# CURRENT_MEASURE.net
KiCad netlist of a schematic drawn in Altium Designer
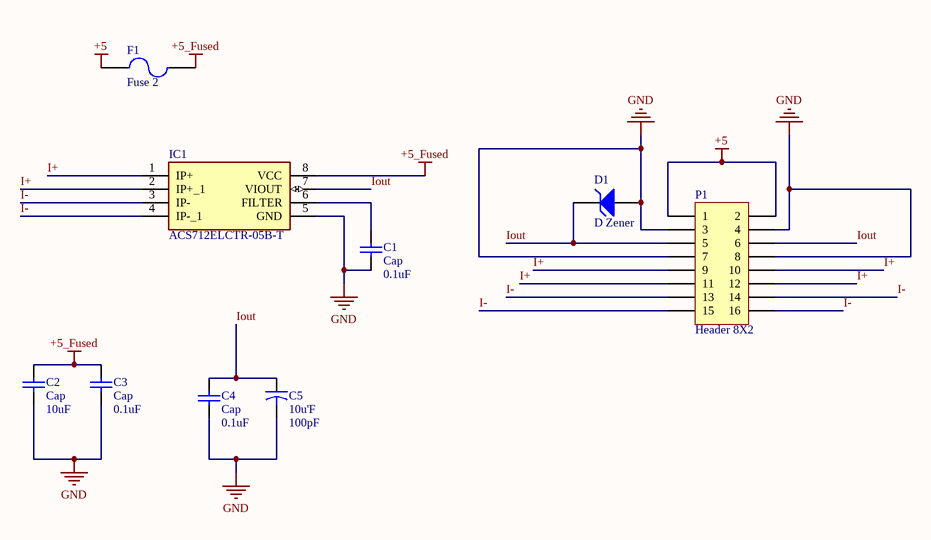
[diagram p0: CURRENT_MEASURE.SchDoc]

(export (version "E")
  (design (tool "Eeschema 10.0.6"))
  (components
    (comp (ref "C1")
      (value "Cap")
      (footprint "1608[0603]")
      (description "Capacitor")
      (fields (field (name "ALTIUM_VALUE") "0.1uF") (field (name "PUBLISHER") "Altium Limited"))
      (libsource (lib "Miscellaneous Devices") (part "Cap"))
    )
    (comp (ref "C2")
      (value "Cap")
      (footprint "C1210")
      (description "Capacitor")
      (fields (field (name "ALTIUM_VALUE") "10uF") (field (name "PUBLISHER") "Altium Limited"))
      (libsource (lib "Miscellaneous Devices") (part "Cap"))
    )
    (comp (ref "C3")
      (value "Cap")
      (footprint "1608[0603]")
      (description "Capacitor")
      (fields (field (name "ALTIUM_VALUE") "0.1uF") (field (name "PUBLISHER") "Altium Limited"))
      (libsource (lib "Miscellaneous Devices") (part "Cap"))
    )
    (comp (ref "C4")
      (value "Cap")
      (footprint "1608[0603]")
      (description "Capacitor")
      (fields (field (name "ALTIUM_VALUE") "0.1uF") (field (name "PUBLISHER") "Altium Limited"))
      (libsource (lib "Miscellaneous Devices") (part "Cap"))
    )
    (comp (ref "C5")
      (value "10u'F")
      (footprint "CAP-6")
      (description "Capacitor")
      (fields (field (name "ALTIUM_VALUE") "100pF") (field (name "PUBLISHER") "Altium Limited"))
      (libsource (lib "Miscellaneous Devices") (part "Cap2"))
    )
    (comp (ref "D1")
      (value "D Zener")
      (footprint "C1206")
      (description "Zener Diode")
      (fields (field (name "PUBLISHER") "Altium Limited"))
      (libsource (lib "Miscellaneous Devices") (part "D Zener"))
    )
    (comp (ref "F1")
      (value "Fuse 2")
      (footprint "C1206")
      (description "Fuse")
      (fields (field (name "PUBLISHER") "Altium Limited"))
      (libsource (lib "Miscellaneous Devices") (part "Fuse 2"))
    )
    (comp (ref "IC1")
      (value "ACS712ELCTR-05B-T")
      (footprint "SamacSys:SOIC127P600X175-8N")
      (description "Integrated Circuit")
      (fields (field (name "RS PART NUMBER") "1729270"))
      (libsource (lib "SamacSys") (part "ACS712ELCTR-05B-T"))
    )
    (comp (ref "P1")
      (value "Header 8X2")
      (footprint "HDR2X8")
      (description "Header, 8-Pin, Dual row")
      (fields (field (name "PUBLISHER") "Altium Limited"))
      (libsource (lib "Miscellaneous Connectors") (part "Header 8X2"))
    )
  )
  (nets
    (net (code "1") (name "+5") (class "Default")
      (node (ref "F1") (pin "2") (pinfunction "2_2") (pintype "passive"))
      (node (ref "P1") (pin "1") (pinfunction "1_1") (pintype "passive"))
      (node (ref "P1") (pin "2") (pinfunction "2_2") (pintype "passive"))
    )
    (net (code "2") (name "+5_Fused") (class "Default")
      (node (ref "C2") (pin "2") (pinfunction "2_2") (pintype "passive"))
      (node (ref "C3") (pin "1") (pinfunction "1_1") (pintype "passive"))
      (node (ref "F1") (pin "1") (pinfunction "1_1") (pintype "passive"))
      (node (ref "IC1") (pin "8") (pinfunction "VCC_8") (pintype "power_in"))
    )
    (net (code "3") (name "/I+") (class "Default")
      (node (ref "IC1") (pin "1") (pinfunction "IP+_1") (pintype "passive"))
      (node (ref "IC1") (pin "2") (pinfunction "IP+_1_2") (pintype "passive"))
      (node (ref "P1") (pin "10") (pinfunction "10_10") (pintype "passive"))
      (node (ref "P1") (pin "11") (pinfunction "11_11") (pintype "passive"))
      (node (ref "P1") (pin "12") (pinfunction "12_12") (pintype "passive"))
      (node (ref "P1") (pin "9") (pinfunction "9_9") (pintype "passive"))
    )
    (net (code "4") (name "/I-") (class "Default")
      (node (ref "IC1") (pin "3") (pinfunction "IP-_3") (pintype "passive"))
      (node (ref "IC1") (pin "4") (pinfunction "IP-_1_4") (pintype "passive"))
      (node (ref "P1") (pin "13") (pinfunction "13_13") (pintype "passive"))
      (node (ref "P1") (pin "14") (pinfunction "14_14") (pintype "passive"))
      (node (ref "P1") (pin "15") (pinfunction "15_15") (pintype "passive"))
      (node (ref "P1") (pin "16") (pinfunction "16_16") (pintype "passive"))
    )
    (net (code "5") (name "/Iout") (class "Default")
      (node (ref "C4") (pin "1") (pinfunction "1_1") (pintype "passive"))
      (node (ref "C5") (pin "1") (pinfunction "1_1") (pintype "passive"))
      (node (ref "D1") (pin "2") (pinfunction "K_2") (pintype "passive"))
      (node (ref "IC1") (pin "7") (pinfunction "VIOUT_7") (pintype "bidirectional"))
      (node (ref "P1") (pin "5") (pinfunction "5_5") (pintype "passive"))
      (node (ref "P1") (pin "6") (pinfunction "6_6") (pintype "passive"))
    )
    (net (code "6") (name "GND") (class "Default")
      (node (ref "C1") (pin "2") (pinfunction "2_2") (pintype "passive"))
      (node (ref "C2") (pin "1") (pinfunction "1_1") (pintype "passive"))
      (node (ref "C3") (pin "2") (pinfunction "2_2") (pintype "passive"))
      (node (ref "C4") (pin "2") (pinfunction "2_2") (pintype "passive"))
      (node (ref "C5") (pin "2") (pinfunction "2_2") (pintype "passive"))
      (node (ref "D1") (pin "1") (pinfunction "A_1") (pintype "passive"))
      (node (ref "IC1") (pin "5") (pinfunction "GND_5") (pintype "power_in"))
      (node (ref "P1") (pin "3") (pinfunction "3_3") (pintype "passive"))
      (node (ref "P1") (pin "4") (pinfunction "4_4") (pintype "passive"))
      (node (ref "P1") (pin "7") (pinfunction "7_7") (pintype "passive"))
      (node (ref "P1") (pin "8") (pinfunction "8_8") (pintype "passive"))
    )
    (net (code "7") (name "Net-(IC1-FILTER)") (class "Default")
      (node (ref "C1") (pin "1") (pinfunction "1_1") (pintype "passive"))
      (node (ref "IC1") (pin "6") (pinfunction "FILTER_6") (pintype "passive"))
    )
  )
)
